# SPDIF-RX.net
KiCad netlist of a schematic drawn in Altium Designer
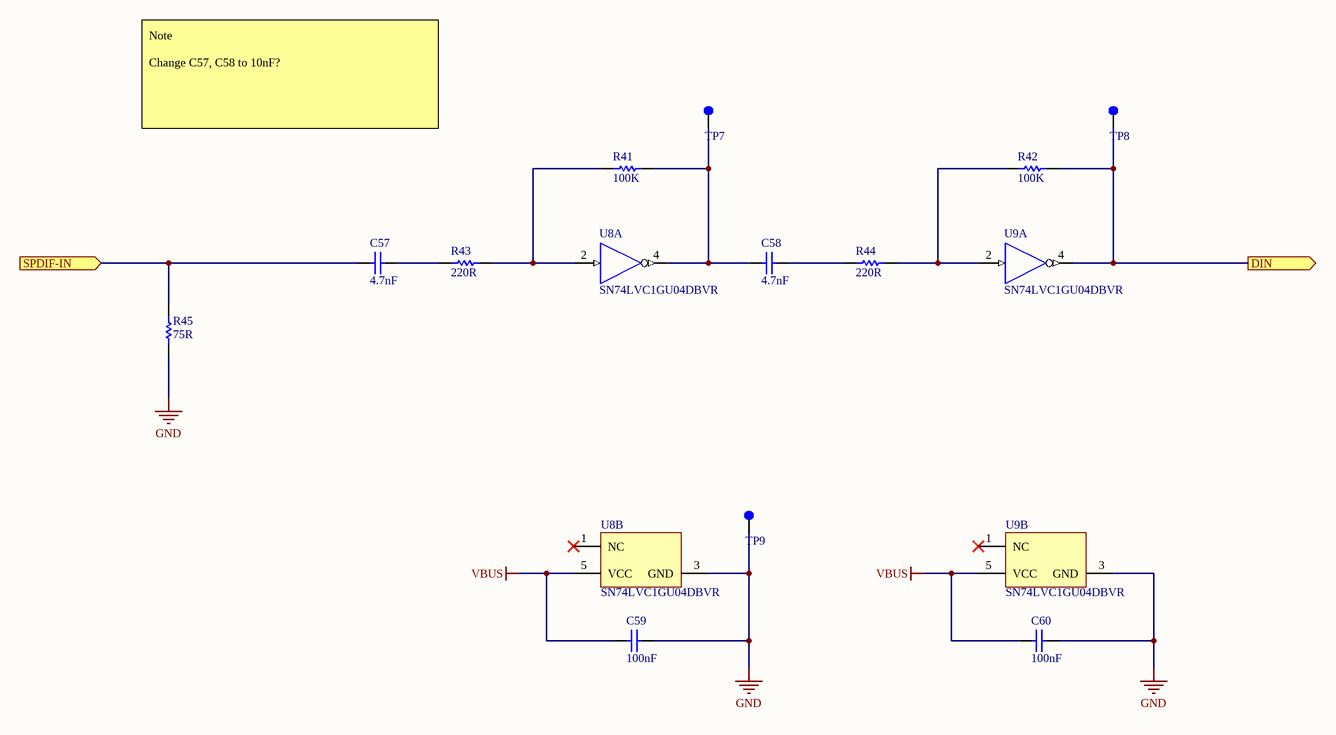
[diagram p0: SPDIF-RX.SchDoc]

(export (version "E")
  (design (tool "Eeschema 10.0.6"))
  (components
    (comp (ref "C57")
      (value "4.7nF")
      (footprint "CAPC0402(1005)33_L")
      (description "0402 4.7nF ±10% 50V X7R")
      (fields (field (name "MPN") "GRM155R71H472KA01D") (field (name "VOLTAGE") "50V"))
      (libsource (lib "seeed") (part "CAP_4.7nF_0402"))
    )
    (comp (ref "C58")
      (value "4.7nF")
      (footprint "CAPC0402(1005)33_L")
      (description "0402 4.7nF ±10% 50V X7R")
      (fields (field (name "MPN") "GRM155R71H472KA01D") (field (name "VOLTAGE") "50V"))
      (libsource (lib "seeed") (part "CAP_4.7nF_0402"))
    )
    (comp (ref "C59")
      (value "100nF")
      (footprint "CAPC0402(1005)33_L")
      (description "0402 100nF ±10% 16V X5R")
      (fields (field (name "MPN") "GRM155R61C104KA88D") (field (name "VOLTAGE") "16V"))
      (libsource (lib "seeed") (part "CAP_100nF_0402"))
    )
    (comp (ref "C60")
      (value "100nF")
      (footprint "CAPC0402(1005)33_L")
      (description "0402 100nF ±10% 16V X5R")
      (fields (field (name "MPN") "GRM155R61C104KA88D") (field (name "VOLTAGE") "16V"))
      (libsource (lib "seeed") (part "CAP_100nF_0402"))
    )
    (comp (ref "R41")
      (value "100K")
      (footprint "RESC0402(1005)_L")
      (description "0402 100KΩ ±1% 1/16W")
      (fields (field (name "TOLERANCE") "1%") (field (name "POWER") "62.5mW"))
      (libsource (lib "seeed") (part "RES_100K_0402"))
    )
    (comp (ref "R42")
      (value "100K")
      (footprint "RESC0402(1005)_L")
      (description "0402 100KΩ ±1% 1/16W")
      (fields (field (name "TOLERANCE") "1%") (field (name "POWER") "62.5mW"))
      (libsource (lib "seeed") (part "RES_100K_0402"))
    )
    (comp (ref "R43")
      (value "220R")
      (footprint "RESC0402(1005)_L")
      (description "0402 220Ω ±1% 1/16W")
      (fields (field (name "TOLERANCE") "1%") (field (name "POWER") "62.5mW"))
      (libsource (lib "seeed") (part "RES_220R_0402"))
    )
    (comp (ref "R44")
      (value "220R")
      (footprint "RESC0402(1005)_L")
      (description "0402 220Ω ±1% 1/16W")
      (fields (field (name "TOLERANCE") "1%") (field (name "POWER") "62.5mW"))
      (libsource (lib "seeed") (part "RES_220R_0402"))
    )
    (comp (ref "R45")
      (value "75R")
      (footprint "RESC0805(2012)_L")
      (description "0805 75Ω ±1% 1/8W")
      (fields (field (name "TOLERANCE") "1%") (field (name "POWER") "62.5mW"))
      (libsource (lib "seeed") (part "RES_75R_0805"))
    )
    (comp (ref "TP7")
      (value "MECH_Testpoint")
      (footprint "MECH_TP_39_mil")
      (description "Testpoint")
      (libsource (lib "micun") (part "MECH_Testpoint"))
    )
    (comp (ref "TP8")
      (value "MECH_Testpoint")
      (footprint "MECH_TP_39_mil")
      (description "Testpoint")
      (libsource (lib "micun") (part "MECH_Testpoint"))
    )
    (comp (ref "TP9")
      (value "MECH_Testpoint")
      (footprint "MECH_TP_39_mil")
      (description "Testpoint")
      (libsource (lib "micun") (part "MECH_Testpoint"))
    )
    (comp (ref "U8")
      (value "SN74LVC1GU04DBVR")
      (footprint "DBV0005A_N")
      (description "Single Inverter Gate, DBV0005A, LARGE T&R")
      (fields (field (name "PART NUMBER") "SN74LVC1GU04"))
      (libsource (lib "Altium Content Vault") (part "TI-SN74XXX1XX4-XX-5"))
    )
    (comp (ref "U9")
      (value "SN74LVC1GU04DBVR")
      (footprint "DBV0005A_N")
      (description "Single Inverter Gate, DBV0005A, LARGE T&R")
      (fields (field (name "PART NUMBER") "SN74LVC1GU04"))
      (libsource (lib "Altium Content Vault") (part "TI-SN74XXX1XX4-XX-5"))
    )
  )
  (nets
    (net (code "1") (name "/DIN") (class "Default")
      (node (ref "R42") (pin "2") (pinfunction "2_2") (pintype "passive"))
      (node (ref "TP8") (pin "1") (pinfunction "Pin1_1") (pintype "passive"))
      (node (ref "U9") (pin "4") (pinfunction "Y_4") (pintype "output"))
    )
    (net (code "2") (name "/SPDIF-IN") (class "Default")
      (node (ref "C57") (pin "1") (pinfunction "1_1") (pintype "passive"))
      (node (ref "R45") (pin "2") (pinfunction "2_2") (pintype "passive"))
    )
    (net (code "3") (name "GND") (class "Default")
      (node (ref "C59") (pin "2") (pinfunction "2_2") (pintype "passive"))
      (node (ref "C60") (pin "2") (pinfunction "2_2") (pintype "passive"))
      (node (ref "R45") (pin "1") (pinfunction "1_1") (pintype "passive"))
      (node (ref "TP9") (pin "1") (pinfunction "Pin1_1") (pintype "passive"))
      (node (ref "U8") (pin "3") (pinfunction "GND_3") (pintype "power_in"))
      (node (ref "U9") (pin "3") (pinfunction "GND_3") (pintype "power_in"))
    )
    (net (code "4") (name "Net-(C57-Pad2)") (class "Default")
      (node (ref "C57") (pin "2") (pinfunction "2_2") (pintype "passive"))
      (node (ref "R43") (pin "1") (pinfunction "1_1") (pintype "passive"))
    )
    (net (code "5") (name "Net-(C58-Pad2)") (class "Default")
      (node (ref "C58") (pin "2") (pinfunction "2_2") (pintype "passive"))
      (node (ref "R44") (pin "1") (pinfunction "1_1") (pintype "passive"))
    )
    (net (code "6") (name "Net-(TP7-Pin1)") (class "Default")
      (node (ref "C58") (pin "1") (pinfunction "1_1") (pintype "passive"))
      (node (ref "R41") (pin "2") (pinfunction "2_2") (pintype "passive"))
      (node (ref "TP7") (pin "1") (pinfunction "Pin1_1") (pintype "passive"))
      (node (ref "U8") (pin "4") (pinfunction "Y_4") (pintype "output"))
    )
    (net (code "7") (name "Net-(U8A-A)") (class "Default")
      (node (ref "R41") (pin "1") (pinfunction "1_1") (pintype "passive"))
      (node (ref "R43") (pin "2") (pinfunction "2_2") (pintype "passive"))
      (node (ref "U8") (pin "2") (pinfunction "A_2") (pintype "input"))
    )
    (net (code "8") (name "Net-(U9A-A)") (class "Default")
      (node (ref "R42") (pin "1") (pinfunction "1_1") (pintype "passive"))
      (node (ref "R44") (pin "2") (pinfunction "2_2") (pintype "passive"))
      (node (ref "U9") (pin "2") (pinfunction "A_2") (pintype "input"))
    )
    (net (code "9") (name "VBUS") (class "Default")
      (node (ref "C59") (pin "1") (pinfunction "1_1") (pintype "passive"))
      (node (ref "C60") (pin "1") (pinfunction "1_1") (pintype "passive"))
      (node (ref "U8") (pin "5") (pinfunction "VCC_5") (pintype "power_in"))
      (node (ref "U9") (pin "5") (pinfunction "VCC_5") (pintype "power_in"))
    )
    (net (code "10") (name "unconnected-(U8B-NC-Pad1)") (class "Default")
      (node (ref "U8") (pin "1") (pinfunction "NC_1") (pintype "passive+no_connect"))
    )
    (net (code "11") (name "unconnected-(U9B-NC-Pad1)") (class "Default")
      (node (ref "U9") (pin "1") (pinfunction "NC_1") (pintype "passive+no_connect"))
    )
  )
)
